# AD9834.net
KiCad netlist of a schematic drawn in Altium Designer
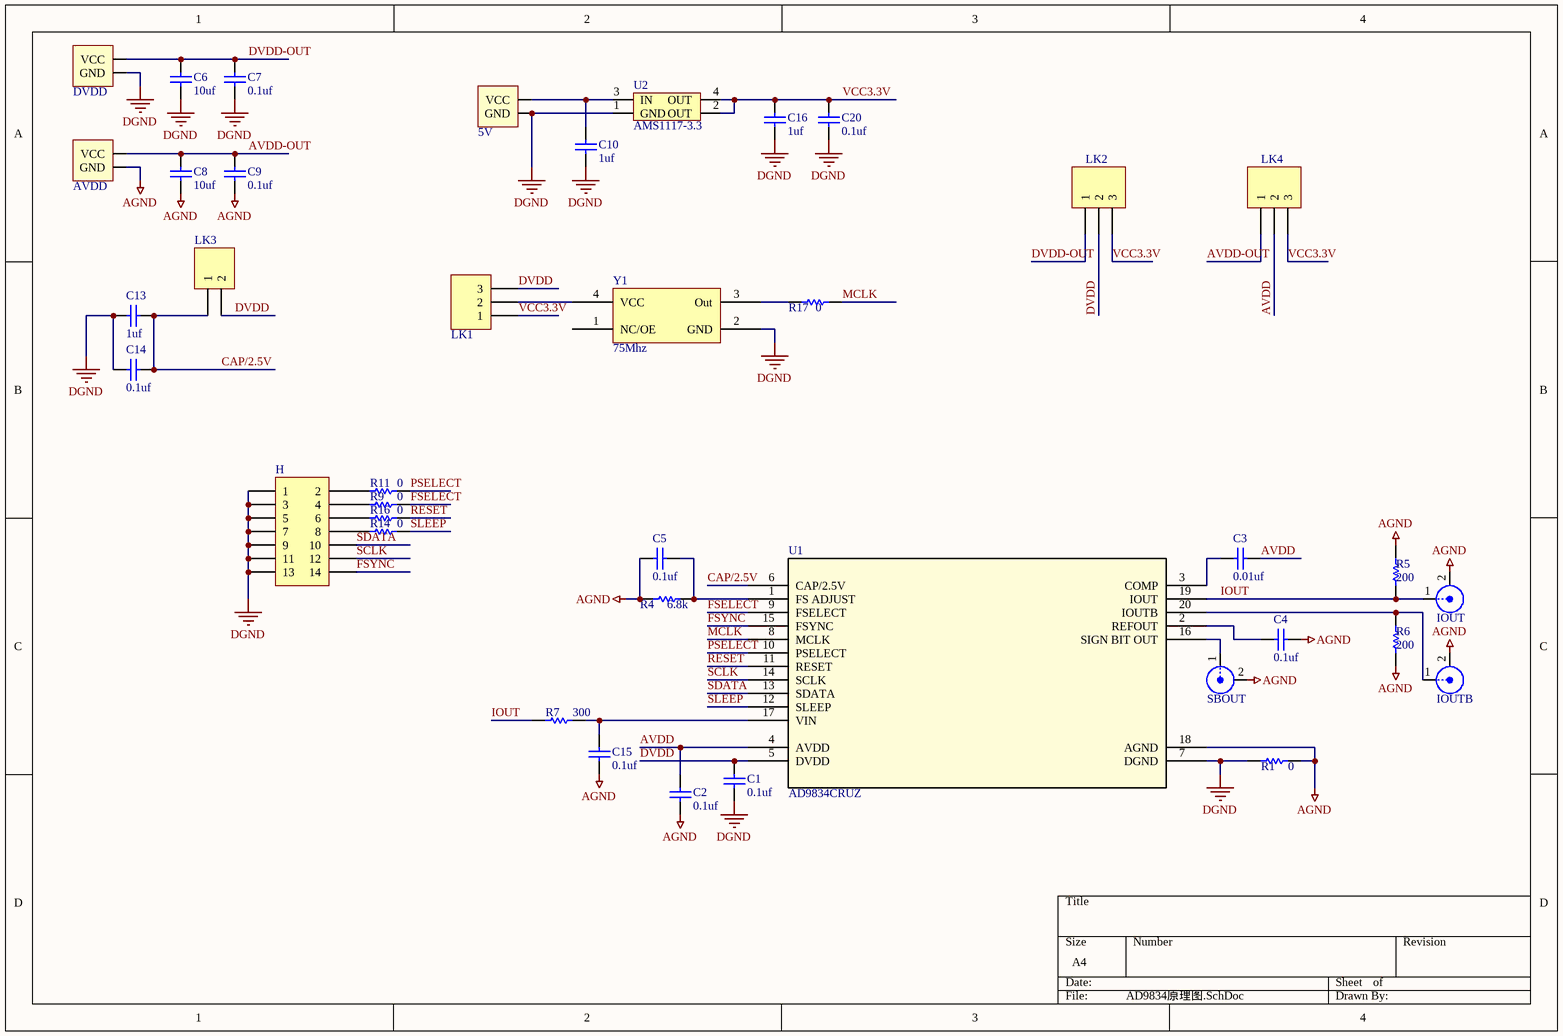
[diagram p0: AD9834原理图.SchDoc]

(export (version "E")
  (design (tool "Eeschema 10.0.6"))
  (components
    (comp (ref "5V")
      (value "Power_2Port")
      (footprint "Power_S_2Port")
      (libsource (lib "电源") (part "Power_2Port"))
    )
    (comp (ref "AVDD")
      (value "Power_2Port")
      (footprint "Power_S_2Port")
      (libsource (lib "电源") (part "Power_2Port"))
    )
    (comp (ref "C1")
      (value "Cap1")
      (footprint "0805")
      (fields (field (name "值") "0.1uf"))
      (libsource (lib "电源") (part "Cap1"))
    )
    (comp (ref "C2")
      (value "Cap1")
      (footprint "0805")
      (fields (field (name "值") "0.1uf"))
      (libsource (lib "电源") (part "Cap1"))
    )
    (comp (ref "C3")
      (value "Cap1")
      (footprint "0805")
      (fields (field (name "值") "0.01uf"))
      (libsource (lib "电源") (part "Cap1"))
    )
    (comp (ref "C4")
      (value "Cap1")
      (footprint "0805")
      (fields (field (name "值") "0.1uf"))
      (libsource (lib "电源") (part "Cap1"))
    )
    (comp (ref "C5")
      (value "Cap1")
      (footprint "0805")
      (fields (field (name "值") "0.1uf"))
      (libsource (lib "电源") (part "Cap1"))
    )
    (comp (ref "C6")
      (value "Cap1")
      (footprint "0805")
      (fields (field (name "值") "10uf"))
      (libsource (lib "电源") (part "Cap1"))
    )
    (comp (ref "C7")
      (value "Cap1")
      (footprint "0805")
      (fields (field (name "值") "0.1uf"))
      (libsource (lib "电源") (part "Cap1"))
    )
    (comp (ref "C8")
      (value "Cap1")
      (footprint "0805")
      (fields (field (name "值") "10uf"))
      (libsource (lib "电源") (part "Cap1"))
    )
    (comp (ref "C9")
      (value "Cap1")
      (footprint "0805")
      (fields (field (name "值") "0.1uf"))
      (libsource (lib "电源") (part "Cap1"))
    )
    (comp (ref "C10")
      (value "Cap1")
      (footprint "0805")
      (fields (field (name "值") "1uf"))
      (libsource (lib "电源") (part "Cap1"))
    )
    (comp (ref "C13")
      (value "Cap1")
      (footprint "0805")
      (fields (field (name "值") "1uf"))
      (libsource (lib "电源") (part "Cap1"))
    )
    (comp (ref "C14")
      (value "Cap1")
      (footprint "0805")
      (fields (field (name "值") "0.1uf"))
      (libsource (lib "电源") (part "Cap1"))
    )
    (comp (ref "C15")
      (value "Cap1")
      (footprint "0805")
      (fields (field (name "值") "0.1uf"))
      (libsource (lib "电源") (part "Cap1"))
    )
    (comp (ref "C16")
      (value "Cap1")
      (footprint "0805")
      (fields (field (name "值") "1uf"))
      (libsource (lib "电源") (part "Cap1"))
    )
    (comp (ref "C20")
      (value "Cap1")
      (footprint "0805")
      (fields (field (name "值") "0.1uf"))
      (libsource (lib "电源") (part "Cap1"))
    )
    (comp (ref "DVDD")
      (value "Power_2Port")
      (footprint "Power_S_2Port")
      (libsource (lib "电源") (part "Power_2Port"))
    )
    (comp (ref "H")
      (value "Header 7X2")
      (footprint "IDC-14")
      (description "Header, 7-Pin, Dual row")
      (fields (field (name "PUBLISHER") "Altium Limited"))
      (libsource (lib "牛角插座") (part "Header 7X2"))
    )
    (comp (ref "IOUT") (value "SMA-2") (footprint "SMA-KE") (libsource (lib "SMA座子") (part "SMA-2")))
    (comp (ref "IOUTB") (value "SMA-2") (footprint "SMA-KE") (libsource (lib "SMA座子") (part "SMA-2")))
    (comp (ref "LK1")
      (value "Header 3")
      (footprint "HDR3X1_A")
      (description "接插件")
      (fields (field (name "PUBLISHER") "Altium Limited"))
      (libsource (lib "Fszhang") (part "Header 3"))
    )
    (comp (ref "LK2")
      (value "Header 3")
      (footprint "HDR3X1_A")
      (description "接插件")
      (fields (field (name "PUBLISHER") "Altium Limited"))
      (libsource (lib "") (part "Header 3_1"))
    )
    (comp (ref "LK3")
      (value "Header 2")
      (footprint "HDR2X1_A")
      (description "接插件")
      (fields (field (name "PUBLISHER") "Altium Limited"))
      (libsource (lib "Fszhang") (part "Header 2"))
    )
    (comp (ref "LK4")
      (value "Header 3")
      (footprint "HDR3X1_A")
      (description "接插件")
      (fields (field (name "PUBLISHER") "Altium Limited"))
      (libsource (lib "") (part "Header 3_1"))
    )
    (comp (ref "R1")
      (value "RES")
      (footprint "0805")
      (fields (field (name "值") "0"))
      (libsource (lib "电源") (part "RES"))
    )
    (comp (ref "R4")
      (value "RES")
      (footprint "0805")
      (fields (field (name "值") "6.8k"))
      (libsource (lib "电源") (part "RES"))
    )
    (comp (ref "R5")
      (value "RES")
      (footprint "0805")
      (fields (field (name "值") "200"))
      (libsource (lib "电源") (part "RES"))
    )
    (comp (ref "R6")
      (value "RES")
      (footprint "0805")
      (fields (field (name "值") "200"))
      (libsource (lib "电源") (part "RES"))
    )
    (comp (ref "R7")
      (value "RES")
      (footprint "0805")
      (fields (field (name "值") "300"))
      (libsource (lib "电源") (part "RES"))
    )
    (comp (ref "R9")
      (value "RES")
      (footprint "0805")
      (fields (field (name "值") "0"))
      (libsource (lib "电源") (part "RES"))
    )
    (comp (ref "R11")
      (value "RES")
      (footprint "0805")
      (fields (field (name "值") "0"))
      (libsource (lib "电源") (part "RES"))
    )
    (comp (ref "R14")
      (value "RES")
      (footprint "0805")
      (fields (field (name "值") "0"))
      (libsource (lib "电源") (part "RES"))
    )
    (comp (ref "R16")
      (value "RES")
      (footprint "0805")
      (fields (field (name "值") "0"))
      (libsource (lib "电源") (part "RES"))
    )
    (comp (ref "R17")
      (value "RES")
      (footprint "0805")
      (fields (field (name "值") "0"))
      (libsource (lib "电源") (part "RES"))
    )
    (comp (ref "SBOUT") (value "SMA-2") (footprint "SMA-KE") (libsource (lib "SMA座子") (part "SMA-2")))
    (comp (ref "U1")
      (value "AD9834CRUZ")
      (footprint "RU_20")
      (description "Imported")
      (libsource (lib "AD9834") (part "AD9834CRUZ"))
    )
    (comp (ref "U2") (value "AMS1117-3.3") (footprint "SOT-223") (libsource (lib "AMS1117") (part "AMS1117")))
    (comp (ref "Y1") (value "75Mhz") (footprint "SMDXTAL5032") (libsource (lib "晶振") (part "XTAL4")))
  )
  (nets
    (net (code "1") (name "/AVDD") (class "Default")
      (node (ref "C2") (pin "2") (pinfunction "2_2") (pintype "passive"))
      (node (ref "C3") (pin "2") (pinfunction "2_2") (pintype "passive"))
      (node (ref "LK4") (pin "2") (pinfunction "2_2") (pintype "passive"))
      (node (ref "U1") (pin "4") (pinfunction "AVDD_4") (pintype "power_in"))
    )
    (net (code "2") (name "/AVDD-OUT") (class "Default")
      (node (ref "AVDD") (pin "1") (pinfunction "VCC_1") (pintype "passive"))
      (node (ref "C8") (pin "2") (pinfunction "2_2") (pintype "passive"))
      (node (ref "C9") (pin "2") (pinfunction "2_2") (pintype "passive"))
      (node (ref "LK4") (pin "1") (pinfunction "1_1") (pintype "passive"))
    )
    (net (code "3") (name "/CAP{slash}2.5V") (class "Default")
      (node (ref "C13") (pin "2") (pinfunction "2_2") (pintype "passive"))
      (node (ref "C14") (pin "2") (pinfunction "2_2") (pintype "passive"))
      (node (ref "LK3") (pin "1") (pinfunction "1_1") (pintype "passive"))
      (node (ref "U1") (pin "6") (pinfunction "CAP/2.5V_6") (pintype "passive"))
    )
    (net (code "4") (name "/DVDD") (class "Default")
      (node (ref "C1") (pin "2") (pinfunction "2_2") (pintype "passive"))
      (node (ref "LK1") (pin "3") (pinfunction "3_3") (pintype "passive"))
      (node (ref "LK2") (pin "2") (pinfunction "2_2") (pintype "passive"))
      (node (ref "LK3") (pin "2") (pinfunction "2_2") (pintype "passive"))
      (node (ref "U1") (pin "5") (pinfunction "DVDD_5") (pintype "power_in"))
    )
    (net (code "5") (name "/DVDD-OUT") (class "Default")
      (node (ref "C6") (pin "2") (pinfunction "2_2") (pintype "passive"))
      (node (ref "C7") (pin "2") (pinfunction "2_2") (pintype "passive"))
      (node (ref "DVDD") (pin "1") (pinfunction "VCC_1") (pintype "passive"))
      (node (ref "LK2") (pin "1") (pinfunction "1_1") (pintype "passive"))
    )
    (net (code "6") (name "/FSELECT") (class "Default")
      (node (ref "R9") (pin "2") (pinfunction "2_2") (pintype "passive"))
      (node (ref "U1") (pin "9") (pinfunction "FSELECT_9") (pintype "passive"))
    )
    (net (code "7") (name "/FSYNC") (class "Default")
      (node (ref "H") (pin "14") (pinfunction "14_14") (pintype "passive"))
      (node (ref "U1") (pin "15") (pinfunction "FSYNC_15") (pintype "passive"))
    )
    (net (code "8") (name "/IOUT") (class "Default")
      (node (ref "IOUT") (pin "1") (pinfunction "Signal_1") (pintype "passive"))
      (node (ref "R5") (pin "1") (pinfunction "1_1") (pintype "passive"))
      (node (ref "R7") (pin "1") (pinfunction "1_1") (pintype "passive"))
      (node (ref "U1") (pin "19") (pinfunction "IOUT_19") (pintype "passive"))
    )
    (net (code "9") (name "/MCLK") (class "Default")
      (node (ref "R17") (pin "2") (pinfunction "2_2") (pintype "passive"))
      (node (ref "U1") (pin "8") (pinfunction "MCLK_8") (pintype "passive"))
    )
    (net (code "10") (name "/PSELECT") (class "Default")
      (node (ref "R11") (pin "2") (pinfunction "2_2") (pintype "passive"))
      (node (ref "U1") (pin "10") (pinfunction "PSELECT_10") (pintype "passive"))
    )
    (net (code "11") (name "/RESET") (class "Default")
      (node (ref "R16") (pin "2") (pinfunction "2_2") (pintype "passive"))
      (node (ref "U1") (pin "11") (pinfunction "RESET_11") (pintype "passive"))
    )
    (net (code "12") (name "/SCLK") (class "Default")
      (node (ref "H") (pin "12") (pinfunction "12_12") (pintype "passive"))
      (node (ref "U1") (pin "14") (pinfunction "SCLK_14") (pintype "passive"))
    )
    (net (code "13") (name "/SDATA") (class "Default")
      (node (ref "H") (pin "10") (pinfunction "10_10") (pintype "passive"))
      (node (ref "U1") (pin "13") (pinfunction "SDATA_13") (pintype "passive"))
    )
    (net (code "14") (name "/SLEEP") (class "Default")
      (node (ref "R14") (pin "2") (pinfunction "2_2") (pintype "passive"))
      (node (ref "U1") (pin "12") (pinfunction "SLEEP_12") (pintype "passive"))
    )
    (net (code "15") (name "/VCC3.3V") (class "Default")
      (node (ref "C16") (pin "2") (pinfunction "2_2") (pintype "passive"))
      (node (ref "C20") (pin "2") (pinfunction "2_2") (pintype "passive"))
      (node (ref "LK1") (pin "1") (pinfunction "1_1") (pintype "passive"))
      (node (ref "LK2") (pin "3") (pinfunction "3_3") (pintype "passive"))
      (node (ref "LK4") (pin "3") (pinfunction "3_3") (pintype "passive"))
      (node (ref "U2") (pin "2") (pinfunction "OUT_2") (pintype "passive"))
      (node (ref "U2") (pin "4") (pinfunction "OUT_4") (pintype "passive"))
    )
    (net (code "16") (name "AGND") (class "Default")
      (node (ref "AVDD") (pin "2") (pinfunction "GND_2") (pintype "passive"))
      (node (ref "C15") (pin "1") (pinfunction "1_1") (pintype "passive"))
      (node (ref "C2") (pin "1") (pinfunction "1_1") (pintype "passive"))
      (node (ref "C4") (pin "2") (pinfunction "2_2") (pintype "passive"))
      (node (ref "C5") (pin "1") (pinfunction "1_1") (pintype "passive"))
      (node (ref "C8") (pin "1") (pinfunction "1_1") (pintype "passive"))
      (node (ref "C9") (pin "1") (pinfunction "1_1") (pintype "passive"))
      (node (ref "IOUT") (pin "2") (pinfunction "GND_2") (pintype "passive"))
      (node (ref "IOUTB") (pin "2") (pinfunction "GND_2") (pintype "passive"))
      (node (ref "R1") (pin "2") (pinfunction "2_2") (pintype "passive"))
      (node (ref "R4") (pin "1") (pinfunction "1_1") (pintype "passive"))
      (node (ref "R5") (pin "2") (pinfunction "2_2") (pintype "passive"))
      (node (ref "R6") (pin "1") (pinfunction "1_1") (pintype "passive"))
      (node (ref "SBOUT") (pin "2") (pinfunction "GND_2") (pintype "passive"))
      (node (ref "U1") (pin "18") (pinfunction "AGND_18") (pintype "passive"))
    )
    (net (code "17") (name "DGND") (class "Default")
      (node (ref "5V") (pin "2") (pinfunction "GND_2") (pintype "passive"))
      (node (ref "C1") (pin "1") (pinfunction "1_1") (pintype "passive"))
      (node (ref "C10") (pin "1") (pinfunction "1_1") (pintype "passive"))
      (node (ref "C13") (pin "1") (pinfunction "1_1") (pintype "passive"))
      (node (ref "C14") (pin "1") (pinfunction "1_1") (pintype "passive"))
      (node (ref "C16") (pin "1") (pinfunction "1_1") (pintype "passive"))
      (node (ref "C20") (pin "1") (pinfunction "1_1") (pintype "passive"))
      (node (ref "C6") (pin "1") (pinfunction "1_1") (pintype "passive"))
      (node (ref "C7") (pin "1") (pinfunction "1_1") (pintype "passive"))
      (node (ref "DVDD") (pin "2") (pinfunction "GND_2") (pintype "passive"))
      (node (ref "H") (pin "1") (pinfunction "1_1") (pintype "passive"))
      (node (ref "H") (pin "11") (pinfunction "11_11") (pintype "passive"))
      (node (ref "H") (pin "13") (pinfunction "13_13") (pintype "passive"))
      (node (ref "H") (pin "3") (pinfunction "3_3") (pintype "passive"))
      (node (ref "H") (pin "5") (pinfunction "5_5") (pintype "passive"))
      (node (ref "H") (pin "7") (pinfunction "7_7") (pintype "passive"))
      (node (ref "H") (pin "9") (pinfunction "9_9") (pintype "passive"))
      (node (ref "R1") (pin "1") (pinfunction "1_1") (pintype "passive"))
      (node (ref "U1") (pin "7") (pinfunction "DGND_7") (pintype "passive"))
      (node (ref "U2") (pin "1") (pinfunction "GND_1") (pintype "passive"))
      (node (ref "Y1") (pin "2") (pinfunction "GND_2") (pintype "passive"))
    )
    (net (code "18") (name "Net-(5V-VCC)") (class "Default")
      (node (ref "5V") (pin "1") (pinfunction "VCC_1") (pintype "passive"))
      (node (ref "C10") (pin "2") (pinfunction "2_2") (pintype "passive"))
      (node (ref "U2") (pin "3") (pinfunction "IN_3") (pintype "passive"))
    )
    (net (code "19") (name "Net-(H-Pad2)") (class "Default")
      (node (ref "H") (pin "2") (pinfunction "2_2") (pintype "passive"))
      (node (ref "R11") (pin "1") (pinfunction "1_1") (pintype "passive"))
    )
    (net (code "20") (name "Net-(H-Pad4)") (class "Default")
      (node (ref "H") (pin "4") (pinfunction "4_4") (pintype "passive"))
      (node (ref "R9") (pin "1") (pinfunction "1_1") (pintype "passive"))
    )
    (net (code "21") (name "Net-(H-Pad6)") (class "Default")
      (node (ref "H") (pin "6") (pinfunction "6_6") (pintype "passive"))
      (node (ref "R16") (pin "1") (pinfunction "1_1") (pintype "passive"))
    )
    (net (code "22") (name "Net-(H-Pad8)") (class "Default")
      (node (ref "H") (pin "8") (pinfunction "8_8") (pintype "passive"))
      (node (ref "R14") (pin "1") (pinfunction "1_1") (pintype "passive"))
    )
    (net (code "23") (name "Net-(IOUTB-Signal)") (class "Default")
      (node (ref "IOUTB") (pin "1") (pinfunction "Signal_1") (pintype "passive"))
      (node (ref "R6") (pin "2") (pinfunction "2_2") (pintype "passive"))
      (node (ref "U1") (pin "20") (pinfunction "IOUTB_20") (pintype "passive"))
    )
    (net (code "24") (name "Net-(SBOUT-Signal)") (class "Default")
      (node (ref "SBOUT") (pin "1") (pinfunction "Signal_1") (pintype "passive"))
      (node (ref "U1") (pin "16") (pinfunction "SIGN_BIT_OUT_16") (pintype "passive"))
    )
    (net (code "25") (name "Net-(U1-COMP)") (class "Default")
      (node (ref "C3") (pin "1") (pinfunction "1_1") (pintype "passive"))
      (node (ref "U1") (pin "3") (pinfunction "COMP_3") (pintype "passive"))
    )
    (net (code "26") (name "Net-(U1-FS_ADJUST)") (class "Default")
      (node (ref "C5") (pin "2") (pinfunction "2_2") (pintype "passive"))
      (node (ref "R4") (pin "2") (pinfunction "2_2") (pintype "passive"))
      (node (ref "U1") (pin "1") (pinfunction "FS_ADJUST_1") (pintype "passive"))
    )
    (net (code "27") (name "Net-(U1-REFOUT)") (class "Default")
      (node (ref "C4") (pin "1") (pinfunction "1_1") (pintype "passive"))
      (node (ref "U1") (pin "2") (pinfunction "REFOUT_2") (pintype "passive"))
    )
    (net (code "28") (name "Net-(U1-VIN)") (class "Default")
      (node (ref "C15") (pin "2") (pinfunction "2_2") (pintype "passive"))
      (node (ref "R7") (pin "2") (pinfunction "2_2") (pintype "passive"))
      (node (ref "U1") (pin "17") (pinfunction "VIN_17") (pintype "passive"))
    )
    (net (code "29") (name "Net-(Y1-Out)") (class "Default")
      (node (ref "R17") (pin "1") (pinfunction "1_1") (pintype "passive"))
      (node (ref "Y1") (pin "3") (pinfunction "Out_3") (pintype "passive"))
    )
    (net (code "30") (name "Net-(Y1-VCC)") (class "Default")
      (node (ref "LK1") (pin "2") (pinfunction "2_2") (pintype "passive"))
      (node (ref "Y1") (pin "4") (pinfunction "VCC_4") (pintype "passive"))
    )
    (net (code "31") (name "unconnected-(Y1-NC{slash}OE-Pad1)") (class "Default")
      (node (ref "Y1") (pin "1") (pinfunction "NC/OE_1") (pintype "passive"))
    )
  )
)
